# MAIN.net
KiCad netlist of a schematic drawn in Altium Designer
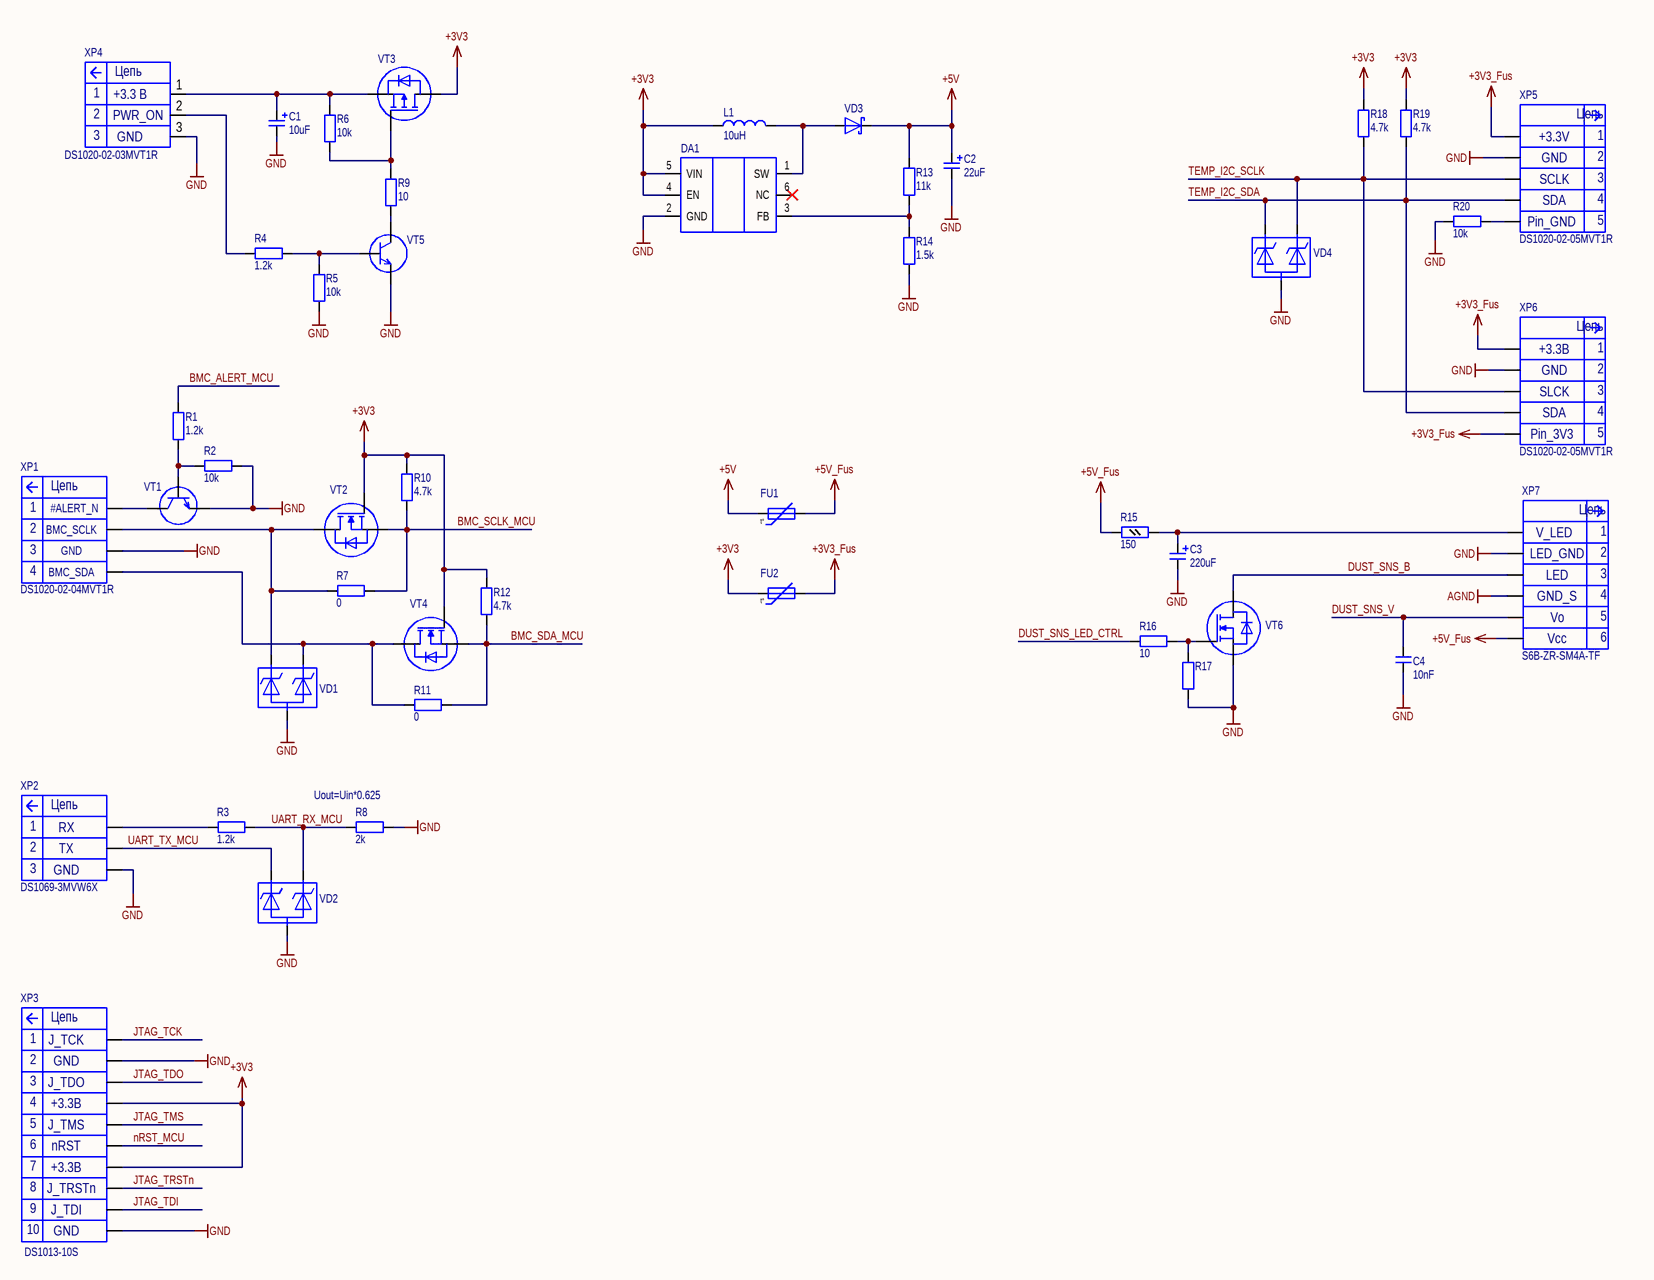
[diagram p0: MAIN.SchDoc]

(export (version "E")
  (design (tool "Eeschema 10.0.6"))
  (components
    (comp (ref "C1")
      (value "10uF")
      (footprint "CAP ALSMD ELEC 4.3MM H5.4MM")
      (description "Конденсатор К50-97 – 25В – 10мкФ (±20) % – ЕВАЯ.673541.054ТУ")
      (fields
        (field (name "MANUFACTURER PART NUMBER") "К50-97 – 25В – 10мкФ (±20) % – ЕВАЯ.673541.054ТУ")
        (field (name "TOLERANCE") "± 20%")
      )
      (libsource (lib "ComponentsDb") (part "Capacitor_Polar"))
    )
    (comp (ref "C2")
      (value "22uF")
      (footprint "CAP ALSMD ELEC 4.3MM H5.4MM")
      (description "Конденсатор К50-97 – 16В – 22мкФ (±20) % – ЕВАЯ.673541.054ТУ")
      (fields
        (field (name "MANUFACTURER PART NUMBER") "К50-97 – 16В – 22мкФ (±20) % – ЕВАЯ.673541.054ТУ")
        (field (name "TOLERANCE") "± 20%")
      )
      (libsource (lib "ComponentsDb") (part "Capacitor_Polar"))
    )
    (comp (ref "C3")
      (value "220uF")
      (footprint "CAP ALSMD ELEC 6.6MM H7.7MM")
      (description "Конденсатор К50-97 – 16В – 220мкФ (±20) % – ЕВАЯ.673541.054ТУ")
      (fields
        (field (name "MANUFACTURER PART NUMBER") "К50-97 – 16В – 220мкФ (±20) % – ЕВАЯ.673541.054ТУ")
        (field (name "TOLERANCE") "± 20%")
      )
      (libsource (lib "ComponentsDb") (part "Capacitor_Polar"))
    )
    (comp (ref "C4")
      (value "10nF")
      (footprint "CAP 0603_1608")
      (description "Конденсатор 0603-X7R-25В-10мкФ ± 10%")
      (fields (field (name "MANUFACTURER PART NUMBER") "GRM188R71E103K") (field (name "TOLERANCE") "± 10%"))
      (libsource (lib "ComponentsDb") (part "Capacitor_Unpolar"))
    )
    (comp (ref "DA1")
      (value "MT3608 AEROSEMI")
      (footprint "TI SOT-23-6 DBV")
      (description "Микросхема MT3608")
      (fields (field (name "MANUFACTURER") "AEROSEMI"))
      (libsource (lib "ComponentsDb") (part "MT3608_AEROSEMI"))
    )
    (comp (ref "FU1")
      (value "BSMD0603-010-15V BHFUSE")
      (footprint "FUSE 0603_1608 0.8MM")
      (description "Предохранитель самовосстанавливающийся BSMD0603-010-15V")
      (fields (field (name "MANUFACTURER") "BHFUSE"))
      (libsource (lib "ComponentsDb") (part "Fuse_PTC"))
    )
    (comp (ref "FU2")
      (value "BSMD0603-010-15V BHFUSE")
      (footprint "FUSE 0603_1608 0.8MM")
      (description "Предохранитель самовосстанавливающийся BSMD0603-010-15V")
      (fields (field (name "MANUFACTURER") "BHFUSE"))
      (libsource (lib "ComponentsDb") (part "Fuse_PTC"))
    )
    (comp (ref "L1")
      (value "10uH")
      (footprint "MURATA LQH32CN")
      (description "Индуктивность 1210-0,45A-10мкГ ± 10%")
      (fields (field (name "MANUFACTURER PART NUMBER") "LQH32CN100K33L") (field (name "TOLERANCE") "± 10%"))
      (libsource (lib "ComponentsDb") (part "Inductor"))
    )
    (comp (ref "R1")
      (value "1.2k")
      (footprint "RES 0603_1608")
      (description "Резистор Р1-12 - 0,1 - 1,2кОм ±1%")
      (fields
        (field (name "MANUFACTURER PART NUMBER") "Р1-12 - 0,1 - 1,2кОм ±1%")
        (field (name "TOLERANCE") "± 1%")
      )
      (libsource (lib "ComponentsDb") (part "Resistor_b"))
    )
    (comp (ref "R2")
      (value "10k")
      (footprint "RES 0603_1608")
      (description "Резистор Р1-12 - 0,1 - 10кОм ±1%")
      (fields
        (field (name "MANUFACTURER PART NUMBER") "Р1-12 - 0,1 - 10кОм ±1%")
        (field (name "TOLERANCE") "± 1%")
      )
      (libsource (lib "ComponentsDb") (part "Resistor_b"))
    )
    (comp (ref "R3")
      (value "1.2k")
      (footprint "RES 0603_1608")
      (description "Резистор Р1-12 - 0,1 - 1,2кОм ±1%")
      (fields
        (field (name "MANUFACTURER PART NUMBER") "Р1-12 - 0,1 - 1,2кОм ±1%")
        (field (name "TOLERANCE") "± 1%")
      )
      (libsource (lib "ComponentsDb") (part "Resistor_b"))
    )
    (comp (ref "R4")
      (value "1.2k")
      (footprint "RES 0603_1608")
      (description "Резистор Р1-12 - 0,1 - 1,2кОм ±1%")
      (fields
        (field (name "MANUFACTURER PART NUMBER") "Р1-12 - 0,1 - 1,2кОм ±1%")
        (field (name "TOLERANCE") "± 1%")
      )
      (libsource (lib "ComponentsDb") (part "Resistor_b"))
    )
    (comp (ref "R5")
      (value "10k")
      (footprint "RES 0603_1608")
      (description "Резистор Р1-12 - 0,1 - 10кОм ±1%")
      (fields
        (field (name "MANUFACTURER PART NUMBER") "Р1-12 - 0,1 - 10кОм ±1%")
        (field (name "TOLERANCE") "± 1%")
      )
      (libsource (lib "ComponentsDb") (part "Resistor_b"))
    )
    (comp (ref "R6")
      (value "10k")
      (footprint "RES 0603_1608")
      (description "Резистор Р1-12 - 0,1 - 10кОм ±1%")
      (fields
        (field (name "MANUFACTURER PART NUMBER") "Р1-12 - 0,1 - 10кОм ±1%")
        (field (name "TOLERANCE") "± 1%")
      )
      (libsource (lib "") (part "Resistor_b_1"))
    )
    (comp (ref "R7")
      (value "0")
      (footprint "RES 0603_1608")
      (description "Перемычка Р1-12 - 0603 - 0,05")
      (fields (field (name "MANUFACTURER PART NUMBER") "Р1-12 - 0603 - 0,05") (field (name "POWER") "3A"))
      (libsource (lib "ComponentsDb") (part "Resistor_b"))
    )
    (comp (ref "R8")
      (value "2k")
      (footprint "RES 0603_1608")
      (description "Резистор Р1-12 - 0,1 - 2кОм ±1%")
      (fields
        (field (name "MANUFACTURER PART NUMBER") "Р1-12 - 0,1 - 2кОм ±1%")
        (field (name "TOLERANCE") "± 1%")
      )
      (libsource (lib "ComponentsDb") (part "Resistor_b"))
    )
    (comp (ref "R9")
      (value "10")
      (footprint "RES 0603_1608")
      (description "Резистор Р1-12 - 0,1 - 10Ом ±1%")
      (fields
        (field (name "MANUFACTURER PART NUMBER") "Р1-12 - 0,1 - 10Ом ±1%")
        (field (name "TOLERANCE") "± 1%")
      )
      (libsource (lib "ComponentsDb") (part "Resistor_b"))
    )
    (comp (ref "R10")
      (value "4.7k")
      (footprint "RES 0603_1608")
      (description "Резистор Р1-12 - 0,1 - 4,7кОм ±1%")
      (fields
        (field (name "MANUFACTURER PART NUMBER") "Р1-12 - 0,1 - 4,7кОм ±1%")
        (field (name "TOLERANCE") "± 1%")
      )
      (libsource (lib "ComponentsDb") (part "Resistor_b"))
    )
    (comp (ref "R11")
      (value "0")
      (footprint "RES 0603_1608")
      (description "Перемычка Р1-12 - 0603 - 0,05")
      (fields (field (name "MANUFACTURER PART NUMBER") "Р1-12 - 0603 - 0,05") (field (name "POWER") "3A"))
      (libsource (lib "ComponentsDb") (part "Resistor_b"))
    )
    (comp (ref "R12")
      (value "4.7k")
      (footprint "RES 0603_1608")
      (description "Резистор Р1-12 - 0,1 - 4,7кОм ±1%")
      (fields
        (field (name "MANUFACTURER PART NUMBER") "Р1-12 - 0,1 - 4,7кОм ±1%")
        (field (name "TOLERANCE") "± 1%")
      )
      (libsource (lib "ComponentsDb") (part "Resistor_b"))
    )
    (comp (ref "R13")
      (value "11k")
      (footprint "RES 0603_1608")
      (description "Резистор Р1-12 - 0,1 - 11кОм ±1%")
      (fields
        (field (name "MANUFACTURER PART NUMBER") "Р1-12 - 0,1 - 11кОм ±1%")
        (field (name "TOLERANCE") "± 1%")
      )
      (libsource (lib "ComponentsDb") (part "Resistor_b"))
    )
    (comp (ref "R14")
      (value "1.5k")
      (footprint "RES 0603_1608")
      (description "Резистор Р1-12 - 0,1 - 1,5кОм ±1%")
      (fields
        (field (name "MANUFACTURER PART NUMBER") "Р1-12 - 0,1 - 1,5кОм ±1%")
        (field (name "TOLERANCE") "± 1%")
      )
      (libsource (lib "ComponentsDb") (part "Resistor_b"))
    )
    (comp (ref "R15")
      (value "150")
      (footprint "RES 0805_2012")
      (description "Резистор Р1-12 - 0,125 - 150Ом ±1%")
      (fields
        (field (name "MANUFACTURER PART NUMBER") "Р1-12 - 0,125 - 150Ом ±1%")
        (field (name "TOLERANCE") "± 1%")
      )
      (libsource (lib "ComponentsDb") (part "Resistor_b_0.125W"))
    )
    (comp (ref "R16")
      (value "10")
      (footprint "RES 0603_1608")
      (description "Резистор Р1-12 - 0,1 - 10Ом ±1%")
      (fields
        (field (name "MANUFACTURER PART NUMBER") "Р1-12 - 0,1 - 10Ом ±1%")
        (field (name "TOLERANCE") "± 1%")
      )
      (libsource (lib "ComponentsDb") (part "Resistor_b"))
    )
    (comp (ref "R17")
      (value "~")
      (footprint "RES 0603_1608")
      (description "Резистор Р1-12 - 0,1 - 10кОм ±1%")
      (fields
        (field (name "MANUFACTURER PART NUMBER") "Р1-12 - 0,1 - 10кОм ±1%")
        (field (name "TOLERANCE") "± 1%")
      )
      (libsource (lib "ComponentsDb") (part "Resistor_b"))
    )
    (comp (ref "R18")
      (value "4.7k")
      (footprint "RES 0603_1608")
      (description "Резистор Р1-12 - 0,1 - 4,7кОм ±1%")
      (fields
        (field (name "MANUFACTURER PART NUMBER") "Р1-12 - 0,1 - 4,7кОм ±1%")
        (field (name "TOLERANCE") "± 1%")
      )
      (libsource (lib "ComponentsDb") (part "Resistor_b"))
    )
    (comp (ref "R19")
      (value "4.7k")
      (footprint "RES 0603_1608")
      (description "Резистор Р1-12 - 0,1 - 4,7кОм ±1%")
      (fields
        (field (name "MANUFACTURER PART NUMBER") "Р1-12 - 0,1 - 4,7кОм ±1%")
        (field (name "TOLERANCE") "± 1%")
      )
      (libsource (lib "ComponentsDb") (part "Resistor_b"))
    )
    (comp (ref "R20")
      (value "10k")
      (footprint "RES 0603_1608")
      (description "Резистор Р1-12 - 0,1 - 10кОм ±1%")
      (fields
        (field (name "MANUFACTURER PART NUMBER") "Р1-12 - 0,1 - 10кОм ±1%")
        (field (name "TOLERANCE") "± 1%")
      )
      (libsource (lib "ComponentsDb") (part "Resistor_b"))
    )
    (comp (ref "VD1")
      (value "PESD5V0U1UT")
      (footprint "SOT-23-3 N")
      (description "Диод ESD PESD5V0U1UT")
      (fields (field (name "MANUFACTURER") "UTD Semiconductor"))
      (libsource (lib "ComponentsDb") (part "Suppresor_UNI_2_CCA"))
    )
    (comp (ref "VD2")
      (value "PESD5V0U1UT")
      (footprint "SOT-23-3 N")
      (description "Диод ESD PESD5V0U1UT")
      (fields (field (name "MANUFACTURER") "UTD Semiconductor"))
      (libsource (lib "ComponentsDb") (part "Suppresor_UNI_2_CCA"))
    )
    (comp (ref "VD3")
      (value "1N5817WS Hottech")
      (footprint "MCC SOD-323")
      (description "Диод Шоттки 1N5817WS")
      (fields (field (name "MANUFACTURER") "Hottech"))
      (libsource (lib "ComponentsDb") (part "Diod_Shottky_AC"))
    )
    (comp (ref "VD4")
      (value "PESD5V0U1UT")
      (footprint "SOT-23-3 N")
      (description "Диод ESD PESD5V0U1UT")
      (fields (field (name "MANUFACTURER") "UTD Semiconductor"))
      (libsource (lib "ComponentsDb") (part "Suppresor_UNI_2_CCA"))
    )
    (comp (ref "VT1")
      (value "КТ229Б9")
      (footprint "SOT-23-3 N")
      (description "Транзистор КТ229Б9 АДКБ.432140.555 ТУ")
      (fields
        (field (name "MANUFACTURER PART NUMBER") "КТ229Б9 АДКБ.432140.555 ТУ")
        (field (name "MANUFACTURER") "Кремний Эл")
      )
      (libsource (lib "ComponentsDb") (part "NPN_BEC"))
    )
    (comp (ref "VT2")
      (value "КП526А9")
      (footprint "SOT-23-3 N")
      (description "Транзистор КП546А9 АДКБ.432140.549")
      (fields
        (field (name "MANUFACTURER PART NUMBER") "КП526А9 АДКБ.432140.549 ТУ")
        (field (name "MANUFACTURER") "Кремний Эл")
      )
      (libsource (lib "ComponentsDb") (part "MOSFET_N-CH_GSD"))
    )
    (comp (ref "VT3")
      (value "AO3401 Hottech")
      (footprint "SOT-23-3 N")
      (description "Транзистор  AO3401 Hottech")
      (fields (field (name "MANUFACTURER") "Hottech"))
      (libsource (lib "ComponentsDb") (part "MOSFET_P-CH_GSD"))
    )
    (comp (ref "VT4")
      (value "КП526А9")
      (footprint "SOT-23-3 N")
      (description "Транзистор КП546А9 АДКБ.432140.549")
      (fields
        (field (name "MANUFACTURER PART NUMBER") "КП526А9 АДКБ.432140.549 ТУ")
        (field (name "MANUFACTURER") "Кремний Эл")
      )
      (libsource (lib "ComponentsDb") (part "MOSFET_N-CH_GSD"))
    )
    (comp (ref "VT5")
      (value "КТ229Б9")
      (footprint "SOT-23-3 N")
      (description "Транзистор КТ229Б9 АДКБ.432140.555 ТУ")
      (fields
        (field (name "MANUFACTURER PART NUMBER") "КТ229Б9 АДКБ.432140.555 ТУ")
        (field (name "MANUFACTURER") "Кремний Эл")
      )
      (libsource (lib "ComponentsDb") (part "NPN_BEC"))
    )
    (comp (ref "VT6")
      (value "КП526А9")
      (footprint "SOT-23-3 N")
      (description "Транзистор КП546А9 АДКБ.432140.549")
      (fields
        (field (name "MANUFACTURER PART NUMBER") "КП526А9 АДКБ.432140.549 ТУ")
        (field (name "MANUFACTURER") "Кремний Эл")
      )
      (libsource (lib "ComponentsDb") (part "MOSFET_N-CH_GSD"))
    )
    (comp (ref "XP1")
      (value "DS1020-02-04MVT1R")
      (footprint "DS1020-02-04MVT1R")
      (description "Соединитель DS1020-02-04MVT1R")
      (fields
        (field (name "NET_4") "BMC_SDA")
        (field (name "NET_3") "GND")
        (field (name "NET_2") "BMC_SCLK")
        (field (name "NET_1") "#ALERT_N")
        (field (name "MANUFACTURER") "Connfly")
      )
      (libsource (lib "ComponentsDb") (part "Plug_4pin"))
    )
    (comp (ref "XP2")
      (value "DS1069-3MVW6X")
      (footprint "CONNFLY_DS1069-3M")
      (description "Соединитель DS1069-3MVW6X")
      (fields
        (field (name "NET_3") "GND")
        (field (name "NET_1") "RX")
        (field (name "NET_2") "TX")
        (field (name "MANUFACTURER") "Connfly")
      )
      (libsource (lib "") (part "Plug_3pin_1"))
    )
    (comp (ref "XP3")
      (value "DS1013-10S")
      (footprint "DS1013-10S")
      (description "Соединитель DS1013-10S")
      (fields
        (field (name "MANUFACTURER") "Connfly")
        (field (name "NET_10") "GND")
        (field (name "NET_9") "J_TDI")
        (field (name "NET_8") "J_TRSTn")
        (field (name "NET_7") "+3.3В")
        (field (name "NET_6") "nRST")
        (field (name "NET_5") "J_TMS")
        (field (name "NET_4") "+3.3В")
        (field (name "NET_3") "J_TDO")
        (field (name "NET_2") "GND")
        (field (name "NET_1") "J_TCK")
      )
      (libsource (lib "ComponentsDb") (part "Plug_10pin"))
    )
    (comp (ref "XP4")
      (value "DS1020-02-03MVT1R")
      (footprint "DS1020-02-03MVT1R")
      (description "Соединитель DS1020-02-03MVT1R")
      (fields
        (field (name "NET_3") "GND")
        (field (name "NET_1") "+3.3 В")
        (field (name "NET_2") "PWR_ON")
        (field (name "MANUFACTURER") "Connfly")
      )
      (libsource (lib "ComponentsDb") (part "Plug_3pin"))
    )
    (comp (ref "XP5")
      (value "DS1020-02-05MVT1R")
      (footprint "DS1020-02-05MVT1R")
      (description "Соединитель DS1020-02-05MVT1R")
      (fields
        (field (name "MANUFACTURER") "Connfly")
        (field (name "NET_5") "Pin_GND")
        (field (name "NET_4") "SDA")
        (field (name "NET_3") "SCLK")
        (field (name "NET_2") "GND")
        (field (name "NET_1") "+3.3V")
      )
      (libsource (lib "ComponentsDb") (part "Plug_5pin"))
    )
    (comp (ref "XP6")
      (value "DS1020-02-05MVT1R")
      (footprint "DS1020-02-05MVT1R")
      (description "Соединитель DS1020-02-05MVT1R")
      (fields
        (field (name "MANUFACTURER") "Connfly")
        (field (name "NET_5") "Pin_3V3")
        (field (name "NET_4") "SDA")
        (field (name "NET_3") "SLCK")
        (field (name "NET_2") "GND")
        (field (name "NET_1") "+3.3В")
      )
      (libsource (lib "") (part "Plug_5pin_1"))
    )
    (comp (ref "XP7")
      (value "S6B-ZR-SM4A-TF")
      (footprint "JST S6B-ZR-SM4A-TF")
      (description "Соединитель S6B-ZR-SM4A-TF")
      (fields
        (field (name "NET_6") "Vcc")
        (field (name "NET_5") "Vo")
        (field (name "NET_4") "GND_S")
        (field (name "NET_3") "LED")
        (field (name "NET_2") "LED_GND")
        (field (name "NET_1") "V_LED")
        (field (name "MANUFACTURER") "JST")
      )
      (libsource (lib "ComponentsDb") (part "Plug_6pin"))
    )
  )
  (nets
    (net (code "1") (name "+3V3") (class "Default")
      (node (ref "DA1") (pin "4") (pinfunction "EN_4") (pintype "power_in"))
      (node (ref "DA1") (pin "5") (pinfunction "VIN_5") (pintype "power_in"))
      (node (ref "FU2") (pin "1") (pinfunction "1_1") (pintype "passive"))
      (node (ref "L1") (pin "1") (pinfunction "P_1") (pintype "passive"))
      (node (ref "R10") (pin "2") (pinfunction "2_2") (pintype "passive"))
      (node (ref "R12") (pin "2") (pinfunction "2_2") (pintype "passive"))
      (node (ref "R18") (pin "2") (pinfunction "2_2") (pintype "passive"))
      (node (ref "R19") (pin "2") (pinfunction "2_2") (pintype "passive"))
      (node (ref "VT2") (pin "1") (pinfunction "G_1") (pintype "passive"))
      (node (ref "VT3") (pin "3") (pinfunction "D_3") (pintype "passive"))
      (node (ref "VT4") (pin "1") (pinfunction "G_1") (pintype "passive"))
      (node (ref "XP3") (pin "4") (pinfunction "4_4") (pintype "passive"))
      (node (ref "XP3") (pin "7") (pinfunction "7_7") (pintype "passive"))
    )
    (net (code "2") (name "+3V3_Fus") (class "Default")
      (node (ref "FU2") (pin "2") (pinfunction "2_2") (pintype "passive"))
      (node (ref "XP5") (pin "1") (pinfunction "1_1") (pintype "passive"))
      (node (ref "XP6") (pin "1") (pinfunction "1_1") (pintype "passive"))
      (node (ref "XP6") (pin "5") (pinfunction "5_5") (pintype "passive"))
    )
    (net (code "3") (name "+5V") (class "Default")
      (node (ref "C2") (pin "1") (pinfunction "P_1") (pintype "passive"))
      (node (ref "FU1") (pin "1") (pinfunction "1_1") (pintype "passive"))
      (node (ref "R13") (pin "2") (pinfunction "2_2") (pintype "passive"))
      (node (ref "VD3") (pin "2") (pinfunction "C_2") (pintype "passive"))
    )
    (net (code "4") (name "+5V_Fus") (class "Default")
      (node (ref "FU1") (pin "2") (pinfunction "2_2") (pintype "passive"))
      (node (ref "R15") (pin "1") (pinfunction "1_1") (pintype "passive"))
      (node (ref "XP7") (pin "6") (pinfunction "6_6") (pintype "passive"))
    )
    (net (code "5") (name "/BMC_ALERT_MCU") (class "Default")
      (node (ref "R1") (pin "2") (pinfunction "2_2") (pintype "passive"))
    )
    (net (code "6") (name "/BMC_SCLK_MCU") (class "Default")
      (node (ref "R10") (pin "1") (pinfunction "1_1") (pintype "passive"))
      (node (ref "R7") (pin "1") (pinfunction "1_1") (pintype "passive"))
      (node (ref "VT2") (pin "2") (pinfunction "S_2") (pintype "passive"))
    )
    (net (code "7") (name "/BMC_SDA_MCU") (class "Default")
      (node (ref "R11") (pin "1") (pinfunction "1_1") (pintype "passive"))
      (node (ref "R12") (pin "1") (pinfunction "1_1") (pintype "passive"))
      (node (ref "VT4") (pin "2") (pinfunction "S_2") (pintype "passive"))
    )
    (net (code "8") (name "/DUST_SNS_B") (class "Default")
      (node (ref "VT6") (pin "3") (pinfunction "D_3") (pintype "passive"))
      (node (ref "XP7") (pin "3") (pinfunction "3_3") (pintype "passive"))
    )
    (net (code "9") (name "/DUST_SNS_LED_CTRL") (class "Default")
      (node (ref "R16") (pin "1") (pinfunction "1_1") (pintype "passive"))
    )
    (net (code "10") (name "/DUST_SNS_V") (class "Default")
      (node (ref "C4") (pin "2") (pinfunction "2_2") (pintype "passive"))
      (node (ref "XP7") (pin "5") (pinfunction "5_5") (pintype "passive"))
    )
    (net (code "11") (name "/JTAG_TCK") (class "Default")
      (node (ref "XP3") (pin "1") (pinfunction "1_1") (pintype "passive"))
    )
    (net (code "12") (name "/JTAG_TDI") (class "Default")
      (node (ref "XP3") (pin "9") (pinfunction "9_9") (pintype "passive"))
    )
    (net (code "13") (name "/JTAG_TDO") (class "Default")
      (node (ref "XP3") (pin "3") (pinfunction "3_3") (pintype "passive"))
    )
    (net (code "14") (name "/JTAG_TMS") (class "Default")
      (node (ref "XP3") (pin "5") (pinfunction "5_5") (pintype "passive"))
    )
    (net (code "15") (name "/JTAG_TRSTn") (class "Default")
      (node (ref "XP3") (pin "8") (pinfunction "8_8") (pintype "passive"))
    )
    (net (code "16") (name "/TEMP_I2C_SCLK") (class "Default")
      (node (ref "R18") (pin "1") (pinfunction "1_1") (pintype "passive"))
      (node (ref "VD4") (pin "2") (pinfunction "C2_2") (pintype "passive"))
      (node (ref "XP5") (pin "3") (pinfunction "3_3") (pintype "passive"))
      (node (ref "XP6") (pin "3") (pinfunction "3_3") (pintype "passive"))
    )
    (net (code "17") (name "/TEMP_I2C_SDA") (class "Default")
      (node (ref "R19") (pin "1") (pinfunction "1_1") (pintype "passive"))
      (node (ref "VD4") (pin "1") (pinfunction "C1_1") (pintype "passive"))
      (node (ref "XP5") (pin "4") (pinfunction "4_4") (pintype "passive"))
      (node (ref "XP6") (pin "4") (pinfunction "4_4") (pintype "passive"))
    )
    (net (code "18") (name "/UART_RX_MCU") (class "Default")
      (node (ref "R3") (pin "2") (pinfunction "2_2") (pintype "passive"))
      (node (ref "R8") (pin "1") (pinfunction "1_1") (pintype "passive"))
      (node (ref "VD2") (pin "2") (pinfunction "C2_2") (pintype "passive"))
    )
    (net (code "19") (name "/UART_TX_MCU") (class "Default")
      (node (ref "VD2") (pin "1") (pinfunction "C1_1") (pintype "passive"))
      (node (ref "XP2") (pin "2") (pinfunction "2_2") (pintype "passive"))
    )
    (net (code "20") (name "/nRST_MCU") (class "Default")
      (node (ref "XP3") (pin "6") (pinfunction "6_6") (pintype "passive"))
    )
    (net (code "21") (name "AGND") (class "Default")
      (node (ref "XP7") (pin "4") (pinfunction "4_4") (pintype "passive"))
    )
    (net (code "22") (name "GND") (class "Default")
      (node (ref "C1") (pin "2") (pinfunction "N_2") (pintype "passive"))
      (node (ref "C2") (pin "2") (pinfunction "N_2") (pintype "passive"))
      (node (ref "C3") (pin "2") (pinfunction "N_2") (pintype "passive"))
      (node (ref "C4") (pin "1") (pinfunction "1_1") (pintype "passive"))
      (node (ref "DA1") (pin "2") (pinfunction "GND_2") (pintype "power_in"))
      (node (ref "R14") (pin "1") (pinfunction "1_1") (pintype "passive"))
      (node (ref "R17") (pin "1") (pinfunction "1_1") (pintype "passive"))
      (node (ref "R2") (pin "1") (pinfunction "1_1") (pintype "passive"))
      (node (ref "R20") (pin "2") (pinfunction "2_2") (pintype "passive"))
      (node (ref "R5") (pin "1") (pinfunction "1_1") (pintype "passive"))
      (node (ref "R8") (pin "2") (pinfunction "2_2") (pintype "passive"))
      (node (ref "VD1") (pin "3") (pinfunction "A_3") (pintype "passive"))
      (node (ref "VD2") (pin "3") (pinfunction "A_3") (pintype "passive"))
      (node (ref "VD4") (pin "3") (pinfunction "A_3") (pintype "passive"))
      (node (ref "VT1") (pin "2") (pinfunction "E_2") (pintype "passive"))
      (node (ref "VT5") (pin "2") (pinfunction "E_2") (pintype "passive"))
      (node (ref "VT6") (pin "2") (pinfunction "S_2") (pintype "passive"))
      (node (ref "XP1") (pin "3") (pinfunction "3_3") (pintype "passive"))
      (node (ref "XP2") (pin "3") (pinfunction "3_3") (pintype "passive"))
      (node (ref "XP3") (pin "10") (pinfunction "10_10") (pintype "passive"))
      (node (ref "XP3") (pin "2") (pinfunction "2_2") (pintype "passive"))
      (node (ref "XP4") (pin "3") (pinfunction "3_3") (pintype "passive"))
      (node (ref "XP5") (pin "2") (pinfunction "2_2") (pintype "passive"))
      (node (ref "XP6") (pin "2") (pinfunction "2_2") (pintype "passive"))
      (node (ref "XP7") (pin "2") (pinfunction "2_2") (pintype "passive"))
    )
    (net (code "23") (name "Net-(C1-P)") (class "Default")
      (node (ref "C1") (pin "1") (pinfunction "P_1") (pintype "passive"))
      (node (ref "R6") (pin "2") (pinfunction "2_2") (pintype "passive"))
      (node (ref "VT3") (pin "2") (pinfunction "S_2") (pintype "passive"))
      (node (ref "XP4") (pin "1") (pinfunction "1_1") (pintype "passive"))
    )
    (net (code "24") (name "Net-(C3-P)") (class "Default")
      (node (ref "C3") (pin "1") (pinfunction "P_1") (pintype "passive"))
      (node (ref "R15") (pin "2") (pinfunction "2_2") (pintype "passive"))
      (node (ref "XP7") (pin "1") (pinfunction "1_1") (pintype "passive"))
    )
    (net (code "25") (name "Net-(DA1-FB)") (class "Default")
      (node (ref "DA1") (pin "3") (pinfunction "FB_3") (pintype "passive"))
      (node (ref "R13") (pin "1") (pinfunction "1_1") (pintype "passive"))
      (node (ref "R14") (pin "2") (pinfunction "2_2") (pintype "passive"))
    )
    (net (code "26") (name "Net-(DA1-SW)") (class "Default")
      (node (ref "DA1") (pin "1") (pinfunction "SW_1") (pintype "power_in"))
      (node (ref "L1") (pin "2") (pinfunction "N_2") (pintype "passive"))
      (node (ref "VD3") (pin "1") (pinfunction "A_1") (pintype "passive"))
    )
    (net (code "27") (name "Net-(R3-Pad1)") (class "Default")
      (node (ref "R3") (pin "1") (pinfunction "1_1") (pintype "passive"))
      (node (ref "XP2") (pin "1") (pinfunction "1_1") (pintype "passive"))
    )
    (net (code "28") (name "Net-(R4-Pad1)") (class "Default")
      (node (ref "R4") (pin "1") (pinfunction "1_1") (pintype "passive"))
      (node (ref "XP4") (pin "2") (pinfunction "2_2") (pintype "passive"))
    )
    (net (code "29") (name "Net-(R20-Pad1)") (class "Default")
      (node (ref "R20") (pin "1") (pinfunction "1_1") (pintype "passive"))
      (node (ref "XP5") (pin "5") (pinfunction "5_5") (pintype "passive"))
    )
    (net (code "30") (name "Net-(VD1-C1)") (class "Default")
      (node (ref "R7") (pin "2") (pinfunction "2_2") (pintype "passive"))
      (node (ref "VD1") (pin "1") (pinfunction "C1_1") (pintype "passive"))
      (node (ref "VT2") (pin "3") (pinfunction "D_3") (pintype "passive"))
      (node (ref "XP1") (pin "2") (pinfunction "2_2") (pintype "passive"))
    )
    (net (code "31") (name "Net-(VD1-C2)") (class "Default")
      (node (ref "R11") (pin "2") (pinfunction "2_2") (pintype "passive"))
      (node (ref "VD1") (pin "2") (pinfunction "C2_2") (pintype "passive"))
      (node (ref "VT4") (pin "3") (pinfunction "D_3") (pintype "passive"))
      (node (ref "XP1") (pin "4") (pinfunction "4_4") (pintype "passive"))
    )
    (net (code "32") (name "Net-(VT1-B)") (class "Default")
      (node (ref "R1") (pin "1") (pinfunction "1_1") (pintype "passive"))
      (node (ref "R2") (pin "2") (pinfunction "2_2") (pintype "passive"))
      (node (ref "VT1") (pin "1") (pinfunction "B_1") (pintype "passive"))
    )
    (net (code "33") (name "Net-(VT1-C)") (class "Default")
      (node (ref "VT1") (pin "3") (pinfunction "C_3") (pintype "passive"))
      (node (ref "XP1") (pin "1") (pinfunction "1_1") (pintype "passive"))
    )
    (net (code "34") (name "Net-(VT3-G)") (class "Default")
      (node (ref "R6") (pin "1") (pinfunction "1_1") (pintype "passive"))
      (node (ref "R9") (pin "1") (pinfunction "1_1") (pintype "passive"))
      (node (ref "VT3") (pin "1") (pinfunction "G_1") (pintype "passive"))
    )
    (net (code "35") (name "Net-(VT5-B)") (class "Default")
      (node (ref "R4") (pin "2") (pinfunction "2_2") (pintype "passive"))
      (node (ref "R5") (pin "2") (pinfunction "2_2") (pintype "passive"))
      (node (ref "VT5") (pin "1") (pinfunction "B_1") (pintype "passive"))
    )
    (net (code "36") (name "Net-(VT5-C)") (class "Default")
      (node (ref "R9") (pin "2") (pinfunction "2_2") (pintype "passive"))
      (node (ref "VT5") (pin "3") (pinfunction "C_3") (pintype "passive"))
    )
    (net (code "37") (name "Net-(VT6-G)") (class "Default")
      (node (ref "R16") (pin "2") (pinfunction "2_2") (pintype "passive"))
      (node (ref "R17") (pin "2") (pinfunction "2_2") (pintype "passive"))
      (node (ref "VT6") (pin "1") (pinfunction "G_1") (pintype "passive"))
    )
    (net (code "38") (name "unconnected-(DA1-NC-Pad6)") (class "Default")
      (node (ref "DA1") (pin "6") (pinfunction "NC_6") (pintype "power_in+no_connect"))
    )
  )
)
